# load_cell_amp_diy.net
KiCad netlist of a schematic drawn in EAGLE
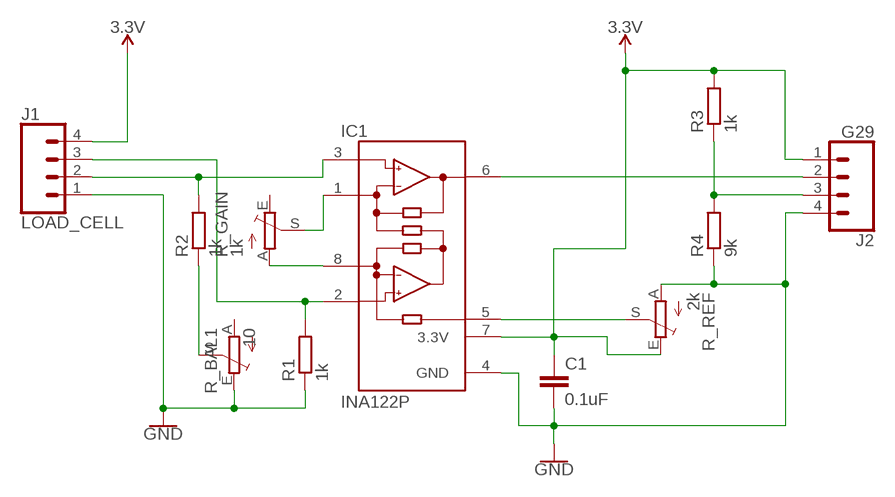
[diagram p0: schematic, sheet 1]

(export (version "E")
  (design (tool "Eeschema 10.0.6"))
  (components
    (comp (ref "C1")
      (value "0.1uF")
      (footprint "eagle-import:C2.5-3")
      (libsource (lib "eagle-import") (part "C2,5-3"))
    )
    (comp (ref "IC1")
      (value "INA122P")
      (footprint "eagle-import:DIL08")
      (fields (field (name "MF") "TEXAS INSTRUMENTS"))
      (libsource (lib "eagle-import") (part "INA122P"))
    )
    (comp (ref "J1")
      (value "LOAD_CELL")
      (footprint "eagle-import:04P")
      (libsource (lib "eagle-import") (part "M04"))
    )
    (comp (ref "J2")
      (value "G29")
      (footprint "eagle-import:04P")
      (libsource (lib "eagle-import") (part "M04"))
    )
    (comp (ref "R1")
      (value "1k")
      (footprint "eagle-import:0207_10")
      (libsource (lib "eagle-import") (part "R-EU_0207/10"))
    )
    (comp (ref "R2")
      (value "1k")
      (footprint "eagle-import:0207_10")
      (libsource (lib "eagle-import") (part "R-EU_0207/10"))
    )
    (comp (ref "R3")
      (value "1k")
      (footprint "eagle-import:0207_10")
      (libsource (lib "eagle-import") (part "R-EU_0207/10"))
    )
    (comp (ref "R4")
      (value "9k")
      (footprint "eagle-import:0207_10")
      (libsource (lib "eagle-import") (part "R-EU_0207/10"))
    )
    (comp (ref "R_BAL1")
      (value "10")
      (footprint "eagle-import:RJ9W")
      (libsource (lib "eagle-import") (part "TRIM_EU-RJ9W"))
    )
    (comp (ref "R_GAIN")
      (value "1k")
      (footprint "eagle-import:RJ9W")
      (libsource (lib "eagle-import") (part "TRIM_EU-RJ9W"))
    )
    (comp (ref "R_REF")
      (value "2k")
      (footprint "eagle-import:RJ9W")
      (libsource (lib "eagle-import") (part "TRIM_EU-RJ9W"))
    )
  )
  (nets
    (net (code "1") (name "3.3V") (class "Default")
      (node (ref "C1") (pin "1") (pinfunction "1_1") (pintype "passive"))
      (node (ref "IC1") (pin "7") (pinfunction "3.3V_7") (pintype "power_in"))
      (node (ref "J1") (pin "4") (pinfunction "4_4") (pintype "passive"))
      (node (ref "J2") (pin "1") (pinfunction "1_1") (pintype "passive"))
      (node (ref "R3") (pin "2") (pinfunction "2_2") (pintype "passive"))
      (node (ref "R_REF") (pin "E") (pinfunction "E_E") (pintype "passive"))
    )
    (net (code "2") (name "GND") (class "Default")
      (node (ref "C1") (pin "2") (pinfunction "2_2") (pintype "passive"))
      (node (ref "IC1") (pin "4") (pinfunction "GND_4") (pintype "power_in"))
      (node (ref "J1") (pin "1") (pinfunction "1_1") (pintype "passive"))
      (node (ref "J2") (pin "4") (pinfunction "4_4") (pintype "passive"))
      (node (ref "R1") (pin "1") (pinfunction "1_1") (pintype "passive"))
      (node (ref "R4") (pin "1") (pinfunction "1_1") (pintype "passive"))
      (node (ref "R_BAL1") (pin "E") (pinfunction "E_E") (pintype "passive"))
      (node (ref "R_REF") (pin "A") (pinfunction "A_A") (pintype "passive"))
    )
    (net (code "3") (name "Net-(IC1-+IN)") (class "Default")
      (node (ref "IC1") (pin "3") (pinfunction "+IN_3") (pintype "input"))
      (node (ref "J1") (pin "2") (pinfunction "2_2") (pintype "passive"))
      (node (ref "R2") (pin "2") (pinfunction "2_2") (pintype "passive"))
    )
    (net (code "4") (name "Net-(IC1--IN)") (class "Default")
      (node (ref "IC1") (pin "2") (pinfunction "-IN_2") (pintype "input"))
      (node (ref "J1") (pin "3") (pinfunction "3_3") (pintype "passive"))
      (node (ref "R1") (pin "2") (pinfunction "2_2") (pintype "passive"))
    )
    (net (code "5") (name "Net-(IC1-OUT)") (class "Default")
      (node (ref "IC1") (pin "6") (pinfunction "OUT_6") (pintype "output"))
      (node (ref "J2") (pin "2") (pinfunction "2_2") (pintype "passive"))
    )
    (net (code "6") (name "Net-(IC1-REF)") (class "Default")
      (node (ref "IC1") (pin "5") (pinfunction "REF_5") (pintype "passive"))
      (node (ref "R_REF") (pin "S") (pinfunction "S_S") (pintype "passive"))
    )
    (net (code "7") (name "Net-(IC1-RG-Pad1)") (class "Default")
      (node (ref "IC1") (pin "1") (pinfunction "RG_1") (pintype "passive"))
      (node (ref "R_GAIN") (pin "S") (pinfunction "S_S") (pintype "passive"))
    )
    (net (code "8") (name "Net-(IC1-RG-Pad8)") (class "Default")
      (node (ref "IC1") (pin "8") (pinfunction "RG_8") (pintype "passive"))
      (node (ref "R_GAIN") (pin "A") (pinfunction "A_A") (pintype "passive"))
    )
    (net (code "9") (name "Net-(J2-Pad3)") (class "Default")
      (node (ref "J2") (pin "3") (pinfunction "3_3") (pintype "passive"))
      (node (ref "R3") (pin "1") (pinfunction "1_1") (pintype "passive"))
      (node (ref "R4") (pin "2") (pinfunction "2_2") (pintype "passive"))
    )
    (net (code "10") (name "Net-(R2-Pad1)") (class "Default")
      (node (ref "R2") (pin "1") (pinfunction "1_1") (pintype "passive"))
      (node (ref "R_BAL1") (pin "S") (pinfunction "S_S") (pintype "passive"))
    )
    (net (code "11") (name "unconnected-(R_BAL1-PadA)") (class "Default")
      (node (ref "R_BAL1") (pin "A") (pinfunction "A_A") (pintype "passive"))
    )
    (net (code "12") (name "unconnected-(R_GAIN-PadE)") (class "Default")
      (node (ref "R_GAIN") (pin "E") (pinfunction "E_E") (pintype "passive"))
    )
  )
)
